# 1.net
KiCad netlist of a schematic drawn in Altium Designer
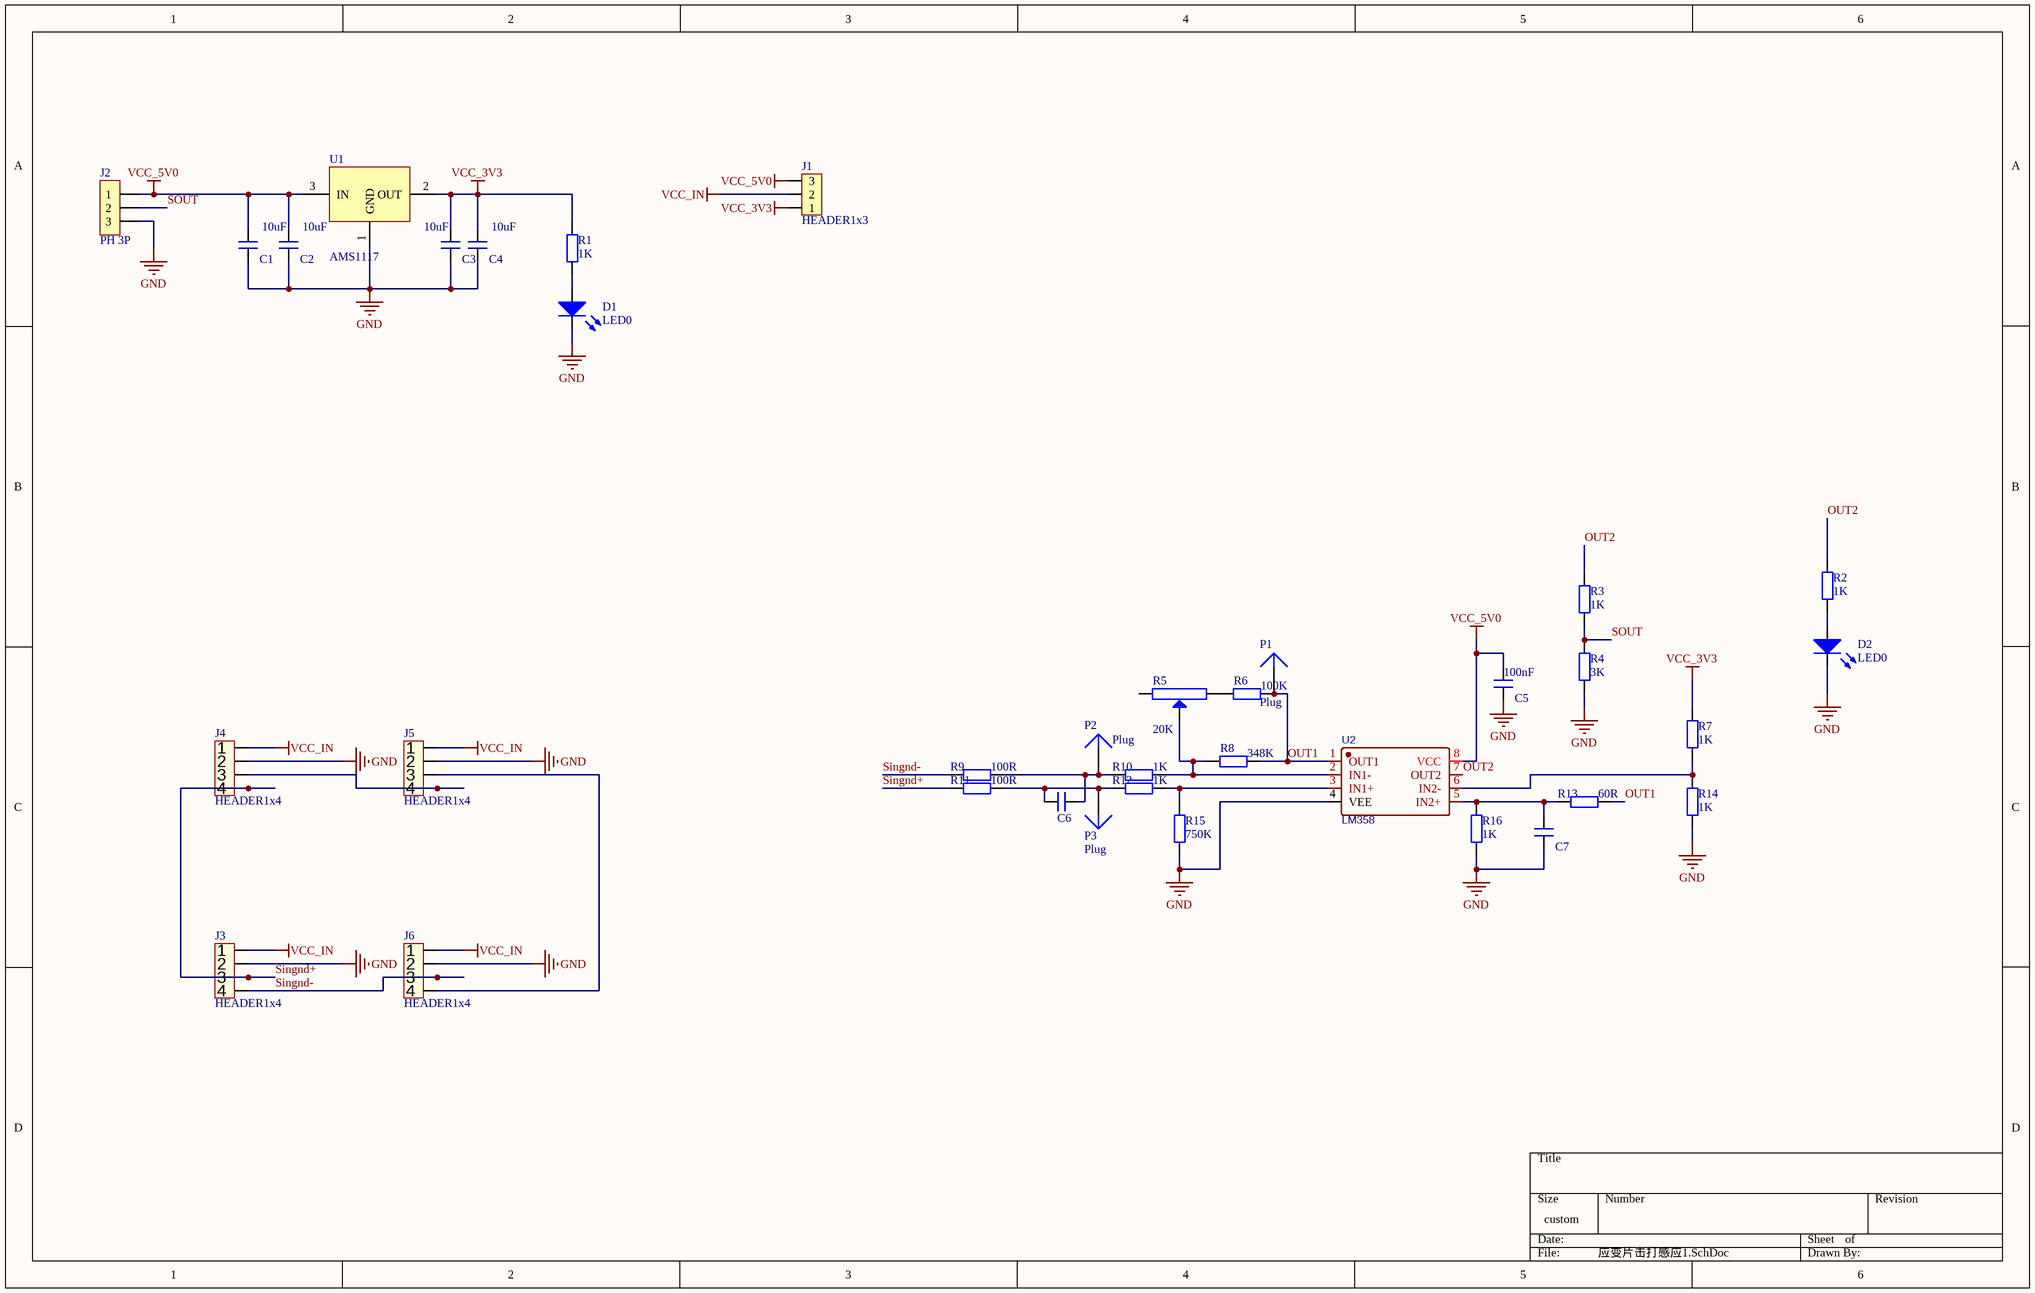
[diagram p0: 应变片击打感应1.SchDoc]

(export (version "E")
  (design (tool "Eeschema 10.0.6"))
  (components
    (comp (ref "C1")
      (value "10uF")
      (footprint "0603_C")
      (fields (field (name "PUBLISHER") "Altium Limited"))
      (libsource (lib "USUAUL") (part "Cap"))
    )
    (comp (ref "C2")
      (value "10uF")
      (footprint "1210_C")
      (fields (field (name "PUBLISHER") "Altium Limited"))
      (libsource (lib "USUAUL") (part "Cap"))
    )
    (comp (ref "C3")
      (value "10uF")
      (footprint "0603_C")
      (fields (field (name "PUBLISHER") "Altium Limited"))
      (libsource (lib "USUAUL") (part "Cap"))
    )
    (comp (ref "C4")
      (value "10uF")
      (footprint "1210_C")
      (fields (field (name "PUBLISHER") "Altium Limited"))
      (libsource (lib "USUAUL") (part "Cap"))
    )
    (comp (ref "C5")
      (value "100nF")
      (footprint "0603_C")
      (fields (field (name "PUBLISHER") "Altium Limited"))
      (libsource (lib "USUAUL") (part "Cap"))
    )
    (comp (ref "C6")
      (value "?uF")
      (footprint "0603_C")
      (fields (field (name "PUBLISHER") "Altium Limited"))
      (libsource (lib "USUAUL") (part "Cap"))
    )
    (comp (ref "C7")
      (value "?uF")
      (footprint "0603_C")
      (fields (field (name "PUBLISHER") "Altium Limited"))
      (libsource (lib "USUAUL") (part "Cap"))
    )
    (comp (ref "D1")
      (value "LED0")
      (footprint "LED-0603")
      (fields (field (name "PUBLISHER") "Altium Limited"))
      (libsource (lib "USUAUL") (part "LED0"))
    )
    (comp (ref "D2")
      (value "LED0")
      (footprint "LED-0603")
      (fields (field (name "PUBLISHER") "Altium Limited"))
      (libsource (lib "USUAUL") (part "LED0"))
    )
    (comp (ref "J1")
      (value "HEADER1x3")
      (footprint "排针排母 3P 2.54mm")
      (libsource (lib "SOCKET") (part "HEADER1x3"))
    )
    (comp (ref "J2") (value "PH 3P") (footprint "XH 3P 2.54mm 立 贴") (libsource (lib "SOCKET") (part "PH 3P")))
    (comp (ref "J3")
      (value "HEADER1x4")
      (footprint "PH 4P 2mm 卧 贴")
      (libsource (lib "SOCKET") (part "HEADER1x4"))
    )
    (comp (ref "J4")
      (value "HEADER1x4")
      (footprint "PH 4P 2mm 卧 贴")
      (libsource (lib "SOCKET") (part "HEADER1x4"))
    )
    (comp (ref "J5")
      (value "HEADER1x4")
      (footprint "PH 4P 2mm 卧 贴")
      (libsource (lib "SOCKET") (part "HEADER1x4"))
    )
    (comp (ref "J6")
      (value "HEADER1x4")
      (footprint "PH 4P 2mm 卧 贴")
      (libsource (lib "SOCKET") (part "HEADER1x4"))
    )
    (comp (ref "P1")
      (value "Plug")
      (footprint "PIN1")
      (fields (field (name "PUBLISHER") "Altium Limited"))
      (libsource (lib "Miscellaneous Connectors") (part "Plug"))
    )
    (comp (ref "P2")
      (value "Plug")
      (footprint "PIN1")
      (fields (field (name "PUBLISHER") "Altium Limited"))
      (libsource (lib "Miscellaneous Connectors") (part "Plug"))
    )
    (comp (ref "P3")
      (value "Plug")
      (footprint "PIN1")
      (fields (field (name "PUBLISHER") "Altium Limited"))
      (libsource (lib "Miscellaneous Connectors") (part "Plug"))
    )
    (comp (ref "R1")
      (value "1K")
      (footprint "0603_R")
      (fields (field (name "PUBLISHER") "Altium Limited"))
      (libsource (lib "USUAUL") (part "Res"))
    )
    (comp (ref "R2")
      (value "1K")
      (footprint "0603_R")
      (fields (field (name "PUBLISHER") "Altium Limited"))
      (libsource (lib "USUAUL") (part "Res"))
    )
    (comp (ref "R3")
      (value "1K")
      (footprint "0603_R")
      (fields (field (name "PUBLISHER") "Altium Limited"))
      (libsource (lib "USUAUL") (part "Res"))
    )
    (comp (ref "R4")
      (value "3K")
      (footprint "0603_R")
      (fields (field (name "PUBLISHER") "Altium Limited"))
      (libsource (lib "USUAUL") (part "Res"))
    )
    (comp (ref "R5") (value "20K") (footprint "3296X") (libsource (lib "USUAUL") (part "精密可调电阻20K")))
    (comp (ref "R6")
      (value "100K")
      (footprint "0603_R")
      (fields (field (name "PUBLISHER") "Altium Limited"))
      (libsource (lib "") (part "Res_1"))
    )
    (comp (ref "R7")
      (value "1K")
      (footprint "0603_R")
      (fields (field (name "PUBLISHER") "Altium Limited"))
      (libsource (lib "USUAUL") (part "Res"))
    )
    (comp (ref "R8")
      (value "348K")
      (footprint "0603_R")
      (fields (field (name "PUBLISHER") "Altium Limited"))
      (libsource (lib "") (part "Res_1"))
    )
    (comp (ref "R9")
      (value "100R")
      (footprint "0603_R")
      (fields (field (name "PUBLISHER") "Altium Limited"))
      (libsource (lib "") (part "Res_1"))
    )
    (comp (ref "R10")
      (value "1K")
      (footprint "0603_R")
      (fields (field (name "PUBLISHER") "Altium Limited"))
      (libsource (lib "") (part "Res_1"))
    )
    (comp (ref "R11")
      (value "100R")
      (footprint "0603_R")
      (fields (field (name "PUBLISHER") "Altium Limited"))
      (libsource (lib "") (part "Res_1"))
    )
    (comp (ref "R12")
      (value "1K")
      (footprint "0603_R")
      (fields (field (name "PUBLISHER") "Altium Limited"))
      (libsource (lib "") (part "Res_1"))
    )
    (comp (ref "R13")
      (value "60R")
      (footprint "0603_R")
      (fields (field (name "PUBLISHER") "Altium Limited"))
      (libsource (lib "") (part "Res_1"))
    )
    (comp (ref "R14")
      (value "1K")
      (footprint "0603_R")
      (fields (field (name "PUBLISHER") "Altium Limited"))
      (libsource (lib "USUAUL") (part "Res"))
    )
    (comp (ref "R15")
      (value "750K")
      (footprint "0603_R")
      (fields (field (name "PUBLISHER") "Altium Limited"))
      (libsource (lib "USUAUL") (part "Res"))
    )
    (comp (ref "R16")
      (value "1K")
      (footprint "0603_R")
      (fields (field (name "PUBLISHER") "Altium Limited"))
      (libsource (lib "USUAUL") (part "Res"))
    )
    (comp (ref "U1")
      (value "AMS1117")
      (footprint "AMS1117")
      (description "线性稳压3.3V-5V 1A")
      (libsource (lib "POWERIC") (part "AMS1117"))
    )
    (comp (ref "U2")
      (value "LM358")
      (footprint "SOP-8")
      (fields (field (name "BOM_SUPPLIER PART") "C328566") (field (name "CONTRIBUTOR") "LCSC"))
      (libsource (lib "OTHERS") (part "LM358"))
    )
  )
  (nets
    (net (code "1") (name "/OUT1") (class "Default")
      (node (ref "P1") (pin "1") (pinfunction "1_1") (pintype "passive"))
      (node (ref "R13") (pin "2") (pinfunction "2_2") (pintype "passive"))
      (node (ref "R6") (pin "2") (pinfunction "2_2") (pintype "passive"))
      (node (ref "R8") (pin "2") (pinfunction "2_2") (pintype "passive"))
      (node (ref "U2") (pin "1") (pinfunction "OUT1_1") (pintype "passive"))
    )
    (net (code "2") (name "/OUT2") (class "Default")
      (node (ref "R2") (pin "2") (pinfunction "2_2") (pintype "passive"))
      (node (ref "R3") (pin "2") (pinfunction "2_2") (pintype "passive"))
      (node (ref "U2") (pin "7") (pinfunction "OUT2_7") (pintype "passive"))
    )
    (net (code "3") (name "/SOUT") (class "Default")
      (node (ref "J2") (pin "2") (pinfunction "2_2") (pintype "power_in"))
      (node (ref "R3") (pin "1") (pinfunction "1_1") (pintype "passive"))
      (node (ref "R4") (pin "2") (pinfunction "2_2") (pintype "passive"))
    )
    (net (code "4") (name "/Singnd+") (class "Default")
      (node (ref "J3") (pin "3") (pinfunction "3_3") (pintype "passive"))
      (node (ref "J4") (pin "4") (pinfunction "4_4") (pintype "passive"))
      (node (ref "R11") (pin "1") (pinfunction "1_1") (pintype "passive"))
    )
    (net (code "5") (name "/Singnd-") (class "Default")
      (node (ref "J3") (pin "4") (pinfunction "4_4") (pintype "passive"))
      (node (ref "J6") (pin "3") (pinfunction "3_3") (pintype "passive"))
      (node (ref "R9") (pin "1") (pinfunction "1_1") (pintype "passive"))
    )
    (net (code "6") (name "GND") (class "Default")
      (node (ref "C1") (pin "1") (pinfunction "1_1") (pintype "passive"))
      (node (ref "C2") (pin "1") (pinfunction "1_1") (pintype "passive"))
      (node (ref "C3") (pin "1") (pinfunction "1_1") (pintype "passive"))
      (node (ref "C4") (pin "1") (pinfunction "1_1") (pintype "passive"))
      (node (ref "C5") (pin "2") (pinfunction "2_2") (pintype "passive"))
      (node (ref "C7") (pin "2") (pinfunction "2_2") (pintype "passive"))
      (node (ref "D1") (pin "2") (pinfunction "K_2") (pintype "passive"))
      (node (ref "D2") (pin "2") (pinfunction "K_2") (pintype "passive"))
      (node (ref "J2") (pin "3") (pinfunction "3_3") (pintype "power_in"))
      (node (ref "J3") (pin "2") (pinfunction "2_2") (pintype "passive"))
      (node (ref "J4") (pin "2") (pinfunction "2_2") (pintype "passive"))
      (node (ref "J5") (pin "2") (pinfunction "2_2") (pintype "passive"))
      (node (ref "J6") (pin "2") (pinfunction "2_2") (pintype "passive"))
      (node (ref "R14") (pin "1") (pinfunction "1_1") (pintype "passive"))
      (node (ref "R15") (pin "1") (pinfunction "1_1") (pintype "passive"))
      (node (ref "R16") (pin "1") (pinfunction "1_1") (pintype "passive"))
      (node (ref "R4") (pin "1") (pinfunction "1_1") (pintype "passive"))
      (node (ref "U1") (pin "1") (pinfunction "GND_1") (pintype "passive"))
      (node (ref "U2") (pin "4") (pinfunction "VEE_4") (pintype "passive"))
    )
    (net (code "7") (name "Net-(C6-Pad1)") (class "Default")
      (node (ref "C6") (pin "1") (pinfunction "1_1") (pintype "passive"))
      (node (ref "P2") (pin "1") (pinfunction "1_1") (pintype "passive"))
      (node (ref "R10") (pin "1") (pinfunction "1_1") (pintype "passive"))
      (node (ref "R9") (pin "2") (pinfunction "2_2") (pintype "passive"))
    )
    (net (code "8") (name "Net-(C6-Pad2)") (class "Default")
      (node (ref "C6") (pin "2") (pinfunction "2_2") (pintype "passive"))
      (node (ref "P3") (pin "1") (pinfunction "1_1") (pintype "passive"))
      (node (ref "R11") (pin "2") (pinfunction "2_2") (pintype "passive"))
      (node (ref "R12") (pin "1") (pinfunction "1_1") (pintype "passive"))
    )
    (net (code "9") (name "Net-(D1-A)") (class "Default")
      (node (ref "D1") (pin "1") (pinfunction "A_1") (pintype "passive"))
      (node (ref "R1") (pin "1") (pinfunction "1_1") (pintype "passive"))
    )
    (net (code "10") (name "Net-(D2-A)") (class "Default")
      (node (ref "D2") (pin "1") (pinfunction "A_1") (pintype "passive"))
      (node (ref "R2") (pin "1") (pinfunction "1_1") (pintype "passive"))
    )
    (net (code "11") (name "Net-(J4-Pad3)") (class "Default")
      (node (ref "J4") (pin "3") (pinfunction "3_3") (pintype "passive"))
      (node (ref "J5") (pin "4") (pinfunction "4_4") (pintype "passive"))
    )
    (net (code "12") (name "Net-(J5-Pad3)") (class "Default")
      (node (ref "J5") (pin "3") (pinfunction "3_3") (pintype "passive"))
      (node (ref "J6") (pin "4") (pinfunction "4_4") (pintype "passive"))
    )
    (net (code "13") (name "Net-(R5-Pad3)") (class "Default")
      (node (ref "R5") (pin "3") (pinfunction "3_3") (pintype "passive"))
      (node (ref "R6") (pin "1") (pinfunction "1_1") (pintype "passive"))
    )
    (net (code "14") (name "Net-(U2-IN1+)") (class "Default")
      (node (ref "R12") (pin "2") (pinfunction "2_2") (pintype "passive"))
      (node (ref "R15") (pin "2") (pinfunction "2_2") (pintype "passive"))
      (node (ref "U2") (pin "3") (pinfunction "IN1+_3") (pintype "passive"))
    )
    (net (code "15") (name "Net-(U2-IN1-)") (class "Default")
      (node (ref "R10") (pin "2") (pinfunction "2_2") (pintype "passive"))
      (node (ref "R5") (pin "2") (pinfunction "2_2") (pintype "passive"))
      (node (ref "R8") (pin "1") (pinfunction "1_1") (pintype "passive"))
      (node (ref "U2") (pin "2") (pinfunction "IN1-_2") (pintype "passive"))
    )
    (net (code "16") (name "Net-(U2-IN2+)") (class "Default")
      (node (ref "C7") (pin "1") (pinfunction "1_1") (pintype "passive"))
      (node (ref "R13") (pin "1") (pinfunction "1_1") (pintype "passive"))
      (node (ref "R16") (pin "2") (pinfunction "2_2") (pintype "passive"))
      (node (ref "U2") (pin "5") (pinfunction "IN2+_5") (pintype "passive"))
    )
    (net (code "17") (name "Net-(U2-IN2-)") (class "Default")
      (node (ref "R14") (pin "2") (pinfunction "2_2") (pintype "passive"))
      (node (ref "R7") (pin "1") (pinfunction "1_1") (pintype "passive"))
      (node (ref "U2") (pin "6") (pinfunction "IN2-_6") (pintype "passive"))
    )
    (net (code "18") (name "VCC_3V3") (class "Default")
      (node (ref "C3") (pin "2") (pinfunction "2_2") (pintype "passive"))
      (node (ref "C4") (pin "2") (pinfunction "2_2") (pintype "passive"))
      (node (ref "J1") (pin "1") (pinfunction "1_1") (pintype "passive"))
      (node (ref "R1") (pin "2") (pinfunction "2_2") (pintype "passive"))
      (node (ref "R7") (pin "2") (pinfunction "2_2") (pintype "passive"))
      (node (ref "U1") (pin "2") (pinfunction "OUT_2") (pintype "passive"))
    )
    (net (code "19") (name "VCC_5V0") (class "Default")
      (node (ref "C1") (pin "2") (pinfunction "2_2") (pintype "passive"))
      (node (ref "C2") (pin "2") (pinfunction "2_2") (pintype "passive"))
      (node (ref "C5") (pin "1") (pinfunction "1_1") (pintype "passive"))
      (node (ref "J1") (pin "3") (pinfunction "3_3") (pintype "passive"))
      (node (ref "J2") (pin "1") (pinfunction "1_1") (pintype "power_in"))
      (node (ref "U1") (pin "3") (pinfunction "IN_3") (pintype "passive"))
      (node (ref "U2") (pin "8") (pinfunction "VCC_8") (pintype "passive"))
    )
    (net (code "20") (name "VCC_IN") (class "Default")
      (node (ref "J1") (pin "2") (pinfunction "2_2") (pintype "passive"))
      (node (ref "J3") (pin "1") (pinfunction "1_1") (pintype "passive"))
      (node (ref "J4") (pin "1") (pinfunction "1_1") (pintype "passive"))
      (node (ref "J5") (pin "1") (pinfunction "1_1") (pintype "passive"))
      (node (ref "J6") (pin "1") (pinfunction "1_1") (pintype "passive"))
    )
    (net (code "21") (name "unconnected-(R5-Pad1)") (class "Default")
      (node (ref "R5") (pin "1") (pinfunction "1_1") (pintype "passive"))
    )
  )
)
